# Coprocessor_Board.net
KiCad netlist of a schematic drawn in EAGLE
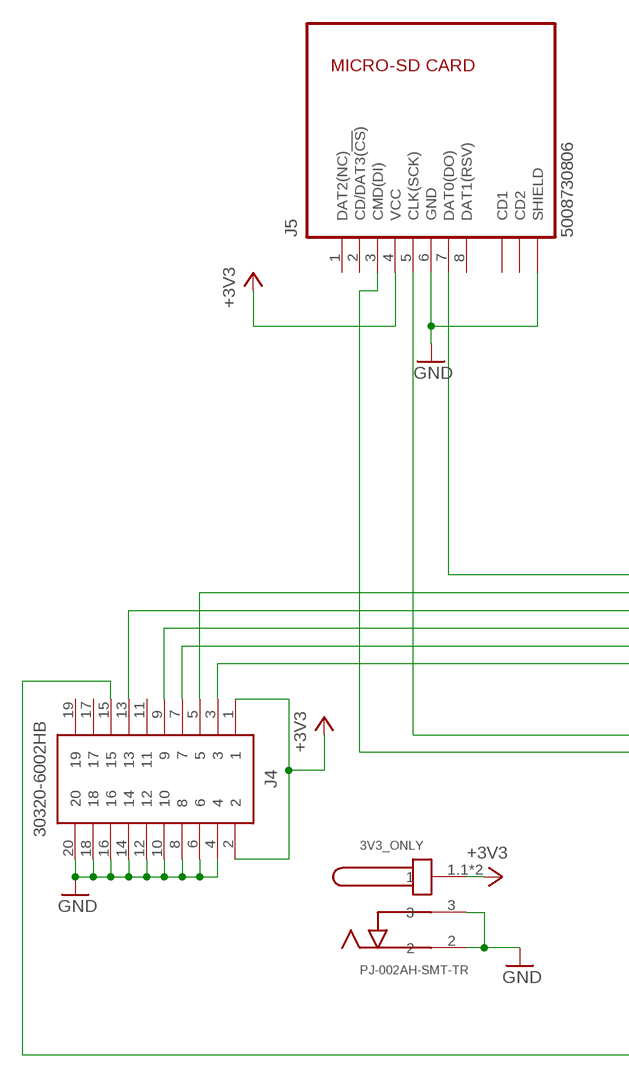
[diagram p0: schematic, sheet 1, part 1 of 2]
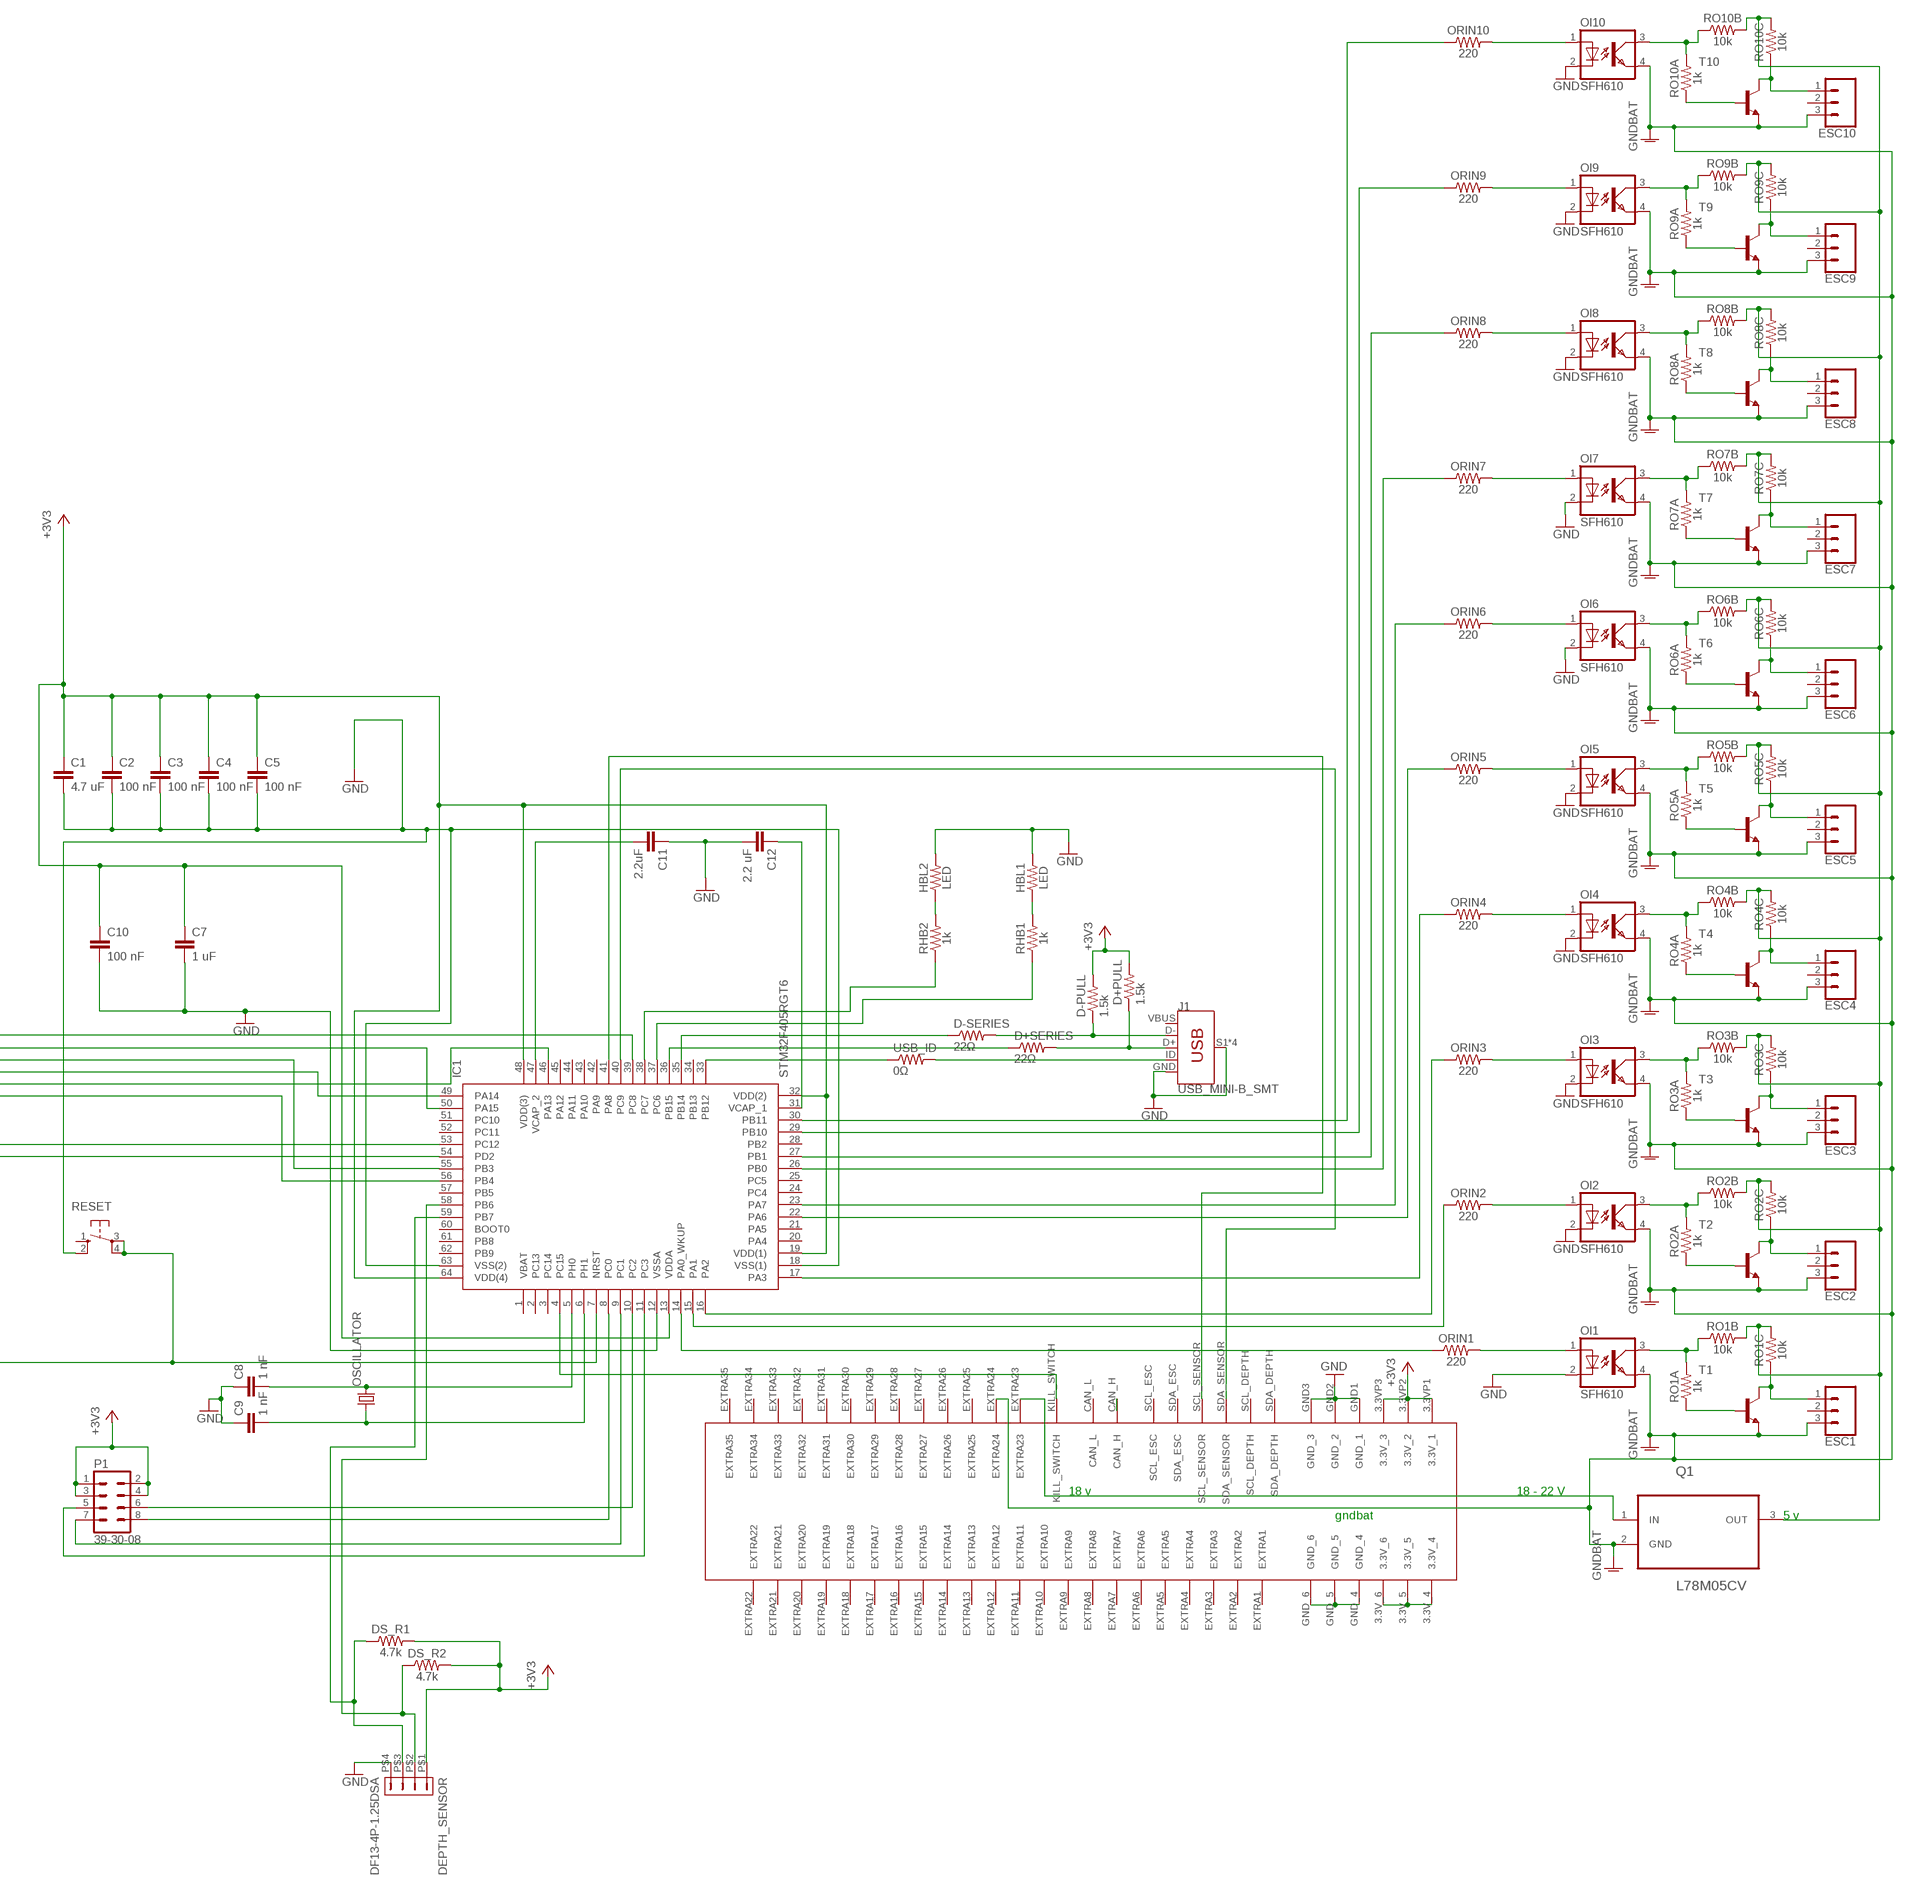
[diagram p1: schematic, sheet 1, part 2 of 2]

(export (version "E")
  (design (tool "Eeschema 10.0.6"))
  (components
    (comp (ref "3V3_ONLY")
      (value "PJ-002AH-SMT-TR")
      (footprint "eagle-import:CUI_PJ-002AH-SMT-TR")
      (fields (field (name "MF") "CUI"))
      (libsource (lib "eagle-import") (part "PJ-002AH-SMT-TR"))
    )
    (comp (ref "C1")
      (value "4.7 uF")
      (footprint "eagle-import:0603")
      (libsource (lib "eagle-import") (part "0.1UF-0603-100V-10%"))
    )
    (comp (ref "C2")
      (value "100 nF")
      (footprint "eagle-import:0603")
      (libsource (lib "eagle-import") (part "0.1UF-0603-100V-10%"))
    )
    (comp (ref "C3")
      (value "100 nF")
      (footprint "eagle-import:0603")
      (libsource (lib "eagle-import") (part "0.1UF-0603-100V-10%"))
    )
    (comp (ref "C4")
      (value "100 nF")
      (footprint "eagle-import:0603")
      (libsource (lib "eagle-import") (part "0.1UF-0603-100V-10%"))
    )
    (comp (ref "C5")
      (value "100 nF")
      (footprint "eagle-import:0603")
      (libsource (lib "eagle-import") (part "0.1UF-0603-100V-10%"))
    )
    (comp (ref "C7")
      (value "1 uF")
      (footprint "eagle-import:0603")
      (libsource (lib "eagle-import") (part "0.1UF-0603-100V-10%"))
    )
    (comp (ref "C8")
      (value "1 nF")
      (footprint "eagle-import:CAP-PTH-2.54")
      (libsource (lib "eagle-import") (part "22PF-PTH-2.54MM-200V-5%"))
    )
    (comp (ref "C9")
      (value "1 nF")
      (footprint "eagle-import:CAP-PTH-2.54")
      (libsource (lib "eagle-import") (part "22PF-PTH-2.54MM-200V-5%"))
    )
    (comp (ref "C10")
      (value "100 nF")
      (footprint "eagle-import:0603")
      (libsource (lib "eagle-import") (part "0.1UF-0603-100V-10%"))
    )
    (comp (ref "C11")
      (value "2.2uF")
      (footprint "eagle-import:0603")
      (libsource (lib "eagle-import") (part "0.1UF-0603-100V-10%"))
    )
    (comp (ref "C12")
      (value "2.2 uF")
      (footprint "eagle-import:0603")
      (libsource (lib "eagle-import") (part "0.1UF-0603-100V-10%"))
    )
    (comp (ref "D+PULL")
      (value "1.5k")
      (footprint "eagle-import:0204_7")
      (libsource (lib "eagle-import") (part "R-US_0204/7"))
    )
    (comp (ref "D+SERIES")
      (value "22Ω")
      (footprint "eagle-import:0204_7")
      (libsource (lib "eagle-import") (part "R-US_0204/7"))
    )
    (comp (ref "D-PULL")
      (value "1.5k")
      (footprint "eagle-import:0204_7")
      (libsource (lib "eagle-import") (part "R-US_0204/7"))
    )
    (comp (ref "D-SERIES")
      (value "22Ω")
      (footprint "eagle-import:0204_7")
      (libsource (lib "eagle-import") (part "R-US_0204/7"))
    )
    (comp (ref "DEPTH_SENSOR")
      (value "DF13-4P-1.25DSA")
      (footprint "eagle-import:DF13-4P-1.25DSA")
      (libsource (lib "eagle-import") (part "DF13-4P-1.25DSA"))
    )
    (comp (ref "DS_R1")
      (value "4.7k")
      (footprint "eagle-import:AXIAL-0.1")
      (libsource (lib "eagle-import") (part "1KOHM-VERT-1/4W-1%"))
    )
    (comp (ref "DS_R2")
      (value "4.7k")
      (footprint "eagle-import:AXIAL-0.1")
      (libsource (lib "eagle-import") (part "1KOHM-VERT-1/4W-1%"))
    )
    (comp (ref "ESC1")
      (value "CONN_03")
      (footprint "eagle-import:1X03")
      (libsource (lib "eagle-import") (part "CONN_03"))
    )
    (comp (ref "ESC2")
      (value "CONN_03")
      (footprint "eagle-import:1X03")
      (libsource (lib "eagle-import") (part "CONN_03"))
    )
    (comp (ref "ESC3")
      (value "CONN_03")
      (footprint "eagle-import:1X03")
      (libsource (lib "eagle-import") (part "CONN_03"))
    )
    (comp (ref "ESC4")
      (value "CONN_03")
      (footprint "eagle-import:1X03")
      (libsource (lib "eagle-import") (part "CONN_03"))
    )
    (comp (ref "ESC5")
      (value "CONN_03")
      (footprint "eagle-import:1X03")
      (libsource (lib "eagle-import") (part "CONN_03"))
    )
    (comp (ref "ESC6")
      (value "CONN_03")
      (footprint "eagle-import:1X03")
      (libsource (lib "eagle-import") (part "CONN_03"))
    )
    (comp (ref "ESC7")
      (value "CONN_03")
      (footprint "eagle-import:1X03")
      (libsource (lib "eagle-import") (part "CONN_03"))
    )
    (comp (ref "ESC8")
      (value "CONN_03")
      (footprint "eagle-import:1X03")
      (libsource (lib "eagle-import") (part "CONN_03"))
    )
    (comp (ref "ESC9")
      (value "CONN_03")
      (footprint "eagle-import:1X03")
      (libsource (lib "eagle-import") (part "CONN_03"))
    )
    (comp (ref "ESC10")
      (value "CONN_03")
      (footprint "eagle-import:1X03")
      (libsource (lib "eagle-import") (part "CONN_03"))
    )
    (comp (ref "HBL1")
      (value "LED")
      (footprint "eagle-import:AXIAL-0.1")
      (libsource (lib "eagle-import") (part "1KOHM-VERT-1/4W-1%"))
    )
    (comp (ref "HBL2")
      (value "LED")
      (footprint "eagle-import:AXIAL-0.1")
      (libsource (lib "eagle-import") (part "1KOHM-VERT-1/4W-1%"))
    )
    (comp (ref "IC1")
      (value "STM32F405RGT6")
      (footprint "eagle-import:QFP50P1200X1200X160-64N")
      (fields (field (name "RS_PART_NUMBER") "7468217"))
      (libsource (lib "eagle-import") (part "STM32F405RGT6"))
    )
    (comp (ref "J1")
      (value "USB_MINI-B_SMT")
      (footprint "eagle-import:USB-MINIB")
      (libsource (lib "eagle-import") (part "USB_MINI-B_SMT"))
    )
    (comp (ref "J4")
      (value "30320-6002HB")
      (footprint "eagle-import:SHDR20W81P254_2X10_3300X840X93")
      (fields (field (name "RS_PART_NUMBER") "8273587"))
      (libsource (lib "eagle-import") (part "30320-6002HB"))
    )
    (comp (ref "J5")
      (value "5008730806")
      (footprint "eagle-import:5008730806")
      (fields (field (name "MF") "Molex") (field (name "MP") "500873-0806"))
      (libsource (lib "eagle-import") (part "5008730806"))
    )
    (comp (ref "OI1")
      (value "SFH610")
      (footprint "eagle-import:DIL04")
      (fields (field (name "MF") "VISHAY/TELEFUNKEN") (field (name "MPN") "SFH6106-4"))
      (libsource (lib "eagle-import") (part "SFH610"))
    )
    (comp (ref "OI2")
      (value "SFH610")
      (footprint "eagle-import:DIL04")
      (fields (field (name "MF") "VISHAY/TELEFUNKEN") (field (name "MPN") "SFH6106-4"))
      (libsource (lib "eagle-import") (part "SFH610"))
    )
    (comp (ref "OI3")
      (value "SFH610")
      (footprint "eagle-import:DIL04")
      (fields (field (name "MF") "VISHAY/TELEFUNKEN") (field (name "MPN") "SFH6106-4"))
      (libsource (lib "eagle-import") (part "SFH610"))
    )
    (comp (ref "OI4")
      (value "SFH610")
      (footprint "eagle-import:DIL04")
      (fields (field (name "MF") "VISHAY/TELEFUNKEN") (field (name "MPN") "SFH6106-4"))
      (libsource (lib "eagle-import") (part "SFH610"))
    )
    (comp (ref "OI5")
      (value "SFH610")
      (footprint "eagle-import:DIL04")
      (fields (field (name "MF") "VISHAY/TELEFUNKEN") (field (name "MPN") "SFH6106-4"))
      (libsource (lib "eagle-import") (part "SFH610"))
    )
    (comp (ref "OI6")
      (value "SFH610")
      (footprint "eagle-import:DIL04")
      (fields (field (name "MF") "VISHAY/TELEFUNKEN") (field (name "MPN") "SFH6106-4"))
      (libsource (lib "eagle-import") (part "SFH610"))
    )
    (comp (ref "OI7")
      (value "SFH610")
      (footprint "eagle-import:DIL04")
      (fields (field (name "MF") "VISHAY/TELEFUNKEN") (field (name "MPN") "SFH6106-4"))
      (libsource (lib "eagle-import") (part "SFH610"))
    )
    (comp (ref "OI8")
      (value "SFH610")
      (footprint "eagle-import:DIL04")
      (fields (field (name "MF") "VISHAY/TELEFUNKEN") (field (name "MPN") "SFH6106-4"))
      (libsource (lib "eagle-import") (part "SFH610"))
    )
    (comp (ref "OI9")
      (value "SFH610")
      (footprint "eagle-import:DIL04")
      (fields (field (name "MF") "VISHAY/TELEFUNKEN") (field (name "MPN") "SFH6106-4"))
      (libsource (lib "eagle-import") (part "SFH610"))
    )
    (comp (ref "OI10")
      (value "SFH610")
      (footprint "eagle-import:DIL04")
      (fields (field (name "MF") "VISHAY/TELEFUNKEN") (field (name "MPN") "SFH6106-4"))
      (libsource (lib "eagle-import") (part "SFH610"))
    )
    (comp (ref "ORIN1")
      (value "220")
      (footprint "eagle-import:AXIAL-0.1")
      (libsource (lib "eagle-import") (part "1KOHM-VERT-1/4W-1%"))
    )
    (comp (ref "ORIN2")
      (value "220")
      (footprint "eagle-import:AXIAL-0.1")
      (libsource (lib "eagle-import") (part "1KOHM-VERT-1/4W-1%"))
    )
    (comp (ref "ORIN3")
      (value "220")
      (footprint "eagle-import:AXIAL-0.1")
      (libsource (lib "eagle-import") (part "1KOHM-VERT-1/4W-1%"))
    )
    (comp (ref "ORIN4")
      (value "220")
      (footprint "eagle-import:AXIAL-0.1")
      (libsource (lib "eagle-import") (part "1KOHM-VERT-1/4W-1%"))
    )
    (comp (ref "ORIN5")
      (value "220")
      (footprint "eagle-import:AXIAL-0.1")
      (libsource (lib "eagle-import") (part "1KOHM-VERT-1/4W-1%"))
    )
    (comp (ref "ORIN6")
      (value "220")
      (footprint "eagle-import:AXIAL-0.1")
      (libsource (lib "eagle-import") (part "1KOHM-VERT-1/4W-1%"))
    )
    (comp (ref "ORIN7")
      (value "220")
      (footprint "eagle-import:AXIAL-0.1")
      (libsource (lib "eagle-import") (part "1KOHM-VERT-1/4W-1%"))
    )
    (comp (ref "ORIN8")
      (value "220")
      (footprint "eagle-import:AXIAL-0.1")
      (libsource (lib "eagle-import") (part "1KOHM-VERT-1/4W-1%"))
    )
    (comp (ref "ORIN9")
      (value "220")
      (footprint "eagle-import:AXIAL-0.1")
      (libsource (lib "eagle-import") (part "1KOHM-VERT-1/4W-1%"))
    )
    (comp (ref "ORIN10")
      (value "220")
      (footprint "eagle-import:AXIAL-0.1")
      (libsource (lib "eagle-import") (part "1KOHM-VERT-1/4W-1%"))
    )
    (comp (ref "OSCILLATOR")
      (value "CRYSTALHC49S")
      (footprint "eagle-import:HC49_S")
      (libsource (lib "eagle-import") (part "CRYSTALHC49S"))
    )
    (comp (ref "P1")
      (value "39-30-08")
      (footprint "eagle-import:39-30-_08_")
      (libsource (lib "eagle-import") (part "39-30-?08?"))
    )
    (comp (ref "Q1")
      (value "L78M05CV")
      (footprint "eagle-import:TO254P450X1020X1935-3P")
      (fields (field (name "MF") "STMicroelectronics"))
      (libsource (lib "eagle-import") (part "L78M05CV"))
    )
    (comp (ref "RESET")
      (value "10-XX")
      (footprint "eagle-import:B3F-10XX")
      (fields (field (name "MPN") "B3F-1000"))
      (libsource (lib "eagle-import") (part "10-XX"))
    )
    (comp (ref "RHB1")
      (value "1k")
      (footprint "eagle-import:AXIAL-0.3")
      (libsource (lib "eagle-import") (part "1KOHM-HORIZ-1/4W-1%"))
    )
    (comp (ref "RHB2")
      (value "1k")
      (footprint "eagle-import:AXIAL-0.3")
      (libsource (lib "eagle-import") (part "1KOHM-HORIZ-1/4W-5%"))
    )
    (comp (ref "RO1A")
      (value "1k")
      (footprint "eagle-import:0603")
      (libsource (lib "eagle-import") (part "1KOHM-0603-1/10W-1%"))
    )
    (comp (ref "RO1B")
      (value "10k")
      (footprint "eagle-import:0603")
      (libsource (lib "eagle-import") (part "1KOHM-0603-1/10W-1%"))
    )
    (comp (ref "RO1C")
      (value "10k")
      (footprint "eagle-import:0603")
      (libsource (lib "eagle-import") (part "1KOHM-0603-1/10W-1%"))
    )
    (comp (ref "RO2A")
      (value "1k")
      (footprint "eagle-import:0603")
      (libsource (lib "eagle-import") (part "1KOHM-0603-1/10W-1%"))
    )
    (comp (ref "RO2B")
      (value "10k")
      (footprint "eagle-import:0603")
      (libsource (lib "eagle-import") (part "1KOHM-0603-1/10W-1%"))
    )
    (comp (ref "RO2C")
      (value "10k")
      (footprint "eagle-import:0603")
      (libsource (lib "eagle-import") (part "1KOHM-0603-1/10W-1%"))
    )
    (comp (ref "RO3A")
      (value "1k")
      (footprint "eagle-import:0603")
      (libsource (lib "eagle-import") (part "1KOHM-0603-1/10W-1%"))
    )
    (comp (ref "RO3B")
      (value "10k")
      (footprint "eagle-import:0603")
      (libsource (lib "eagle-import") (part "1KOHM-0603-1/10W-1%"))
    )
    (comp (ref "RO3C")
      (value "10k")
      (footprint "eagle-import:0603")
      (libsource (lib "eagle-import") (part "1KOHM-0603-1/10W-1%"))
    )
    (comp (ref "RO4A")
      (value "1k")
      (footprint "eagle-import:0603")
      (libsource (lib "eagle-import") (part "1KOHM-0603-1/10W-1%"))
    )
    (comp (ref "RO4B")
      (value "10k")
      (footprint "eagle-import:0603")
      (libsource (lib "eagle-import") (part "1KOHM-0603-1/10W-1%"))
    )
    (comp (ref "RO4C")
      (value "10k")
      (footprint "eagle-import:0603")
      (libsource (lib "eagle-import") (part "1KOHM-0603-1/10W-1%"))
    )
    (comp (ref "RO5A")
      (value "1k")
      (footprint "eagle-import:0603")
      (libsource (lib "eagle-import") (part "1KOHM-0603-1/10W-1%"))
    )
    (comp (ref "RO5B")
      (value "10k")
      (footprint "eagle-import:0603")
      (libsource (lib "eagle-import") (part "1KOHM-0603-1/10W-1%"))
    )
    (comp (ref "RO5C")
      (value "10k")
      (footprint "eagle-import:0603")
      (libsource (lib "eagle-import") (part "1KOHM-0603-1/10W-1%"))
    )
    (comp (ref "RO6A")
      (value "1k")
      (footprint "eagle-import:0603")
      (libsource (lib "eagle-import") (part "1KOHM-0603-1/10W-1%"))
    )
    (comp (ref "RO6B")
      (value "10k")
      (footprint "eagle-import:0603")
      (libsource (lib "eagle-import") (part "1KOHM-0603-1/10W-1%"))
    )
    (comp (ref "RO6C")
      (value "10k")
      (footprint "eagle-import:0603")
      (libsource (lib "eagle-import") (part "1KOHM-0603-1/10W-1%"))
    )
    (comp (ref "RO7A")
      (value "1k")
      (footprint "eagle-import:0603")
      (libsource (lib "eagle-import") (part "1KOHM-0603-1/10W-1%"))
    )
    (comp (ref "RO7B")
      (value "10k")
      (footprint "eagle-import:0603")
      (libsource (lib "eagle-import") (part "1KOHM-0603-1/10W-1%"))
    )
    (comp (ref "RO7C")
      (value "10k")
      (footprint "eagle-import:0603")
      (libsource (lib "eagle-import") (part "1KOHM-0603-1/10W-1%"))
    )
    (comp (ref "RO8A")
      (value "1k")
      (footprint "eagle-import:0603")
      (libsource (lib "eagle-import") (part "1KOHM-0603-1/10W-1%"))
    )
    (comp (ref "RO8B")
      (value "10k")
      (footprint "eagle-import:0603")
      (libsource (lib "eagle-import") (part "1KOHM-0603-1/10W-1%"))
    )
    (comp (ref "RO8C")
      (value "10k")
      (footprint "eagle-import:0603")
      (libsource (lib "eagle-import") (part "1KOHM-0603-1/10W-1%"))
    )
    (comp (ref "RO9A")
      (value "1k")
      (footprint "eagle-import:0603")
      (libsource (lib "eagle-import") (part "1KOHM-0603-1/10W-1%"))
    )
    (comp (ref "RO9B")
      (value "10k")
      (footprint "eagle-import:0603")
      (libsource (lib "eagle-import") (part "1KOHM-0603-1/10W-1%"))
    )
    (comp (ref "RO9C")
      (value "10k")
      (footprint "eagle-import:0603")
      (libsource (lib "eagle-import") (part "1KOHM-0603-1/10W-1%"))
    )
    (comp (ref "RO10A")
      (value "1k")
      (footprint "eagle-import:0603")
      (libsource (lib "eagle-import") (part "1KOHM-0603-1/10W-1%"))
    )
    (comp (ref "RO10B")
      (value "10k")
      (footprint "eagle-import:0603")
      (libsource (lib "eagle-import") (part "1KOHM-0603-1/10W-1%"))
    )
    (comp (ref "RO10C")
      (value "10k")
      (footprint "eagle-import:0603")
      (libsource (lib "eagle-import") (part "1KOHM-0603-1/10W-1%"))
    )
    (comp (ref "T1")
      (value "-NPN-TO126V")
      (footprint "eagle-import:TO126V")
      (libsource (lib "eagle-import") (part "-NPN-TO126V"))
    )
    (comp (ref "T2")
      (value "-NPN-TO126V")
      (footprint "eagle-import:TO126V")
      (libsource (lib "eagle-import") (part "-NPN-TO126V"))
    )
    (comp (ref "T3")
      (value "-NPN-TO126V")
      (footprint "eagle-import:TO126V")
      (libsource (lib "eagle-import") (part "-NPN-TO126V"))
    )
    (comp (ref "T4")
      (value "-NPN-TO126V")
      (footprint "eagle-import:TO126V")
      (libsource (lib "eagle-import") (part "-NPN-TO126V"))
    )
    (comp (ref "T5")
      (value "-NPN-TO126V")
      (footprint "eagle-import:TO126V")
      (libsource (lib "eagle-import") (part "-NPN-TO126V"))
    )
    (comp (ref "T6")
      (value "-NPN-TO126V")
      (footprint "eagle-import:TO126V")
      (libsource (lib "eagle-import") (part "-NPN-TO126V"))
    )
    (comp (ref "T7")
      (value "-NPN-TO126V")
      (footprint "eagle-import:TO126V")
      (libsource (lib "eagle-import") (part "-NPN-TO126V"))
    )
    (comp (ref "T8")
      (value "-NPN-TO126V")
      (footprint "eagle-import:TO126V")
      (libsource (lib "eagle-import") (part "-NPN-TO126V"))
    )
    (comp (ref "T9")
      (value "-NPN-TO126V")
      (footprint "eagle-import:TO126V")
      (libsource (lib "eagle-import") (part "-NPN-TO126V"))
    )
    (comp (ref "T10")
      (value "-NPN-TO126V")
      (footprint "eagle-import:TO126V")
      (libsource (lib "eagle-import") (part "-NPN-TO126V"))
    )
    (comp (ref "U$1")
      (value "5530843")
      (footprint "eagle-import:5530843-6-BOARDFINGERS")
      (libsource (lib "eagle-import") (part "5530843"))
    )
    (comp (ref "USB_ID")
      (value "0Ω")
      (footprint "eagle-import:0204_7")
      (libsource (lib "eagle-import") (part "R-US_0204/7"))
    )
  )
  (nets
    (net (code "1") (name "+3V3") (class "Default")
      (node (ref "3V3_ONLY") (pin "1.1") (pinfunction "1_1.1") (pintype "passive"))
      (node (ref "3V3_ONLY") (pin "1.2") (pinfunction "1_1.2") (pintype "passive"))
      (node (ref "C1") (pin "1") (pinfunction "1_1") (pintype "passive"))
      (node (ref "C10") (pin "1") (pinfunction "1_1") (pintype "passive"))
      (node (ref "C2") (pin "1") (pinfunction "1_1") (pintype "passive"))
      (node (ref "C3") (pin "1") (pinfunction "1_1") (pintype "passive"))
      (node (ref "C4") (pin "1") (pinfunction "1_1") (pintype "passive"))
      (node (ref "C5") (pin "1") (pinfunction "1_1") (pintype "passive"))
      (node (ref "C7") (pin "1") (pinfunction "1_1") (pintype "passive"))
      (node (ref "D+PULL") (pin "2") (pinfunction "2_2") (pintype "passive"))
      (node (ref "D-PULL") (pin "2") (pinfunction "2_2") (pintype "passive"))
      (node (ref "DEPTH_SENSOR") (pin "P$1") (pinfunction "1_P$1") (pintype "passive"))
      (node (ref "DS_R1") (pin "P$2") (pinfunction "2_P$2") (pintype "passive"))
      (node (ref "DS_R2") (pin "P$2") (pinfunction "2_P$2") (pintype "passive"))
      (node (ref "IC1") (pin "13") (pinfunction "VDDA_13") (pintype "power_in"))
      (node (ref "IC1") (pin "19") (pinfunction "VDD(1)_19") (pintype "power_in"))
      (node (ref "IC1") (pin "32") (pinfunction "VDD(2)_32") (pintype "power_in"))
      (node (ref "IC1") (pin "48") (pinfunction "VDD(3)_48") (pintype "power_in"))
      (node (ref "IC1") (pin "64") (pinfunction "VDD(4)_64") (pintype "power_in"))
      (node (ref "J4") (pin "1") (pinfunction "1_1") (pintype "passive"))
      (node (ref "J4") (pin "2") (pinfunction "2_2") (pintype "passive"))
      (node (ref "J5") (pin "4") (pinfunction "VCC_4") (pintype "bidirectional"))
      (node (ref "P1") (pin "1") (pinfunction "1_1") (pintype "passive"))
      (node (ref "P1") (pin "2") (pinfunction "2_2") (pintype "passive"))
      (node (ref "P1") (pin "3") (pinfunction "3_3") (pintype "passive"))
      (node (ref "P1") (pin "4") (pinfunction "4_4") (pintype "passive"))
      (node (ref "U$1") (pin "3.3VP1") (pinfunction "3.3V_1_3.3VP1") (pintype "bidirectional"))
      (node (ref "U$1") (pin "3.3VP2") (pinfunction "3.3V_2_3.3VP2") (pintype "bidirectional"))
      (node (ref "U$1") (pin "3.3VP3") (pinfunction "3.3V_3_3.3VP3") (pintype "bidirectional"))
      (node (ref "U$1") (pin "3.3V_4") (pinfunction "3.3V_4_3.3V_4") (pintype "bidirectional"))
      (node (ref "U$1") (pin "3.3V_5") (pinfunction "3.3V_5_3.3V_5") (pintype "bidirectional"))
      (node (ref "U$1") (pin "3.3V_6") (pinfunction "3.3V_6_3.3V_6") (pintype "bidirectional"))
    )
    (net (code "2") (name "/VBUS") (class "Default")
      (node (ref "J1") (pin "VBUS") (pinfunction "VBUS_VBUS") (pintype "power_in"))
    )
    (net (code "3") (name "GND") (class "Default")
      (node (ref "3V3_ONLY") (pin "2") (pinfunction "2_2") (pintype "passive"))
      (node (ref "3V3_ONLY") (pin "3") (pinfunction "3_3") (pintype "passive"))
      (node (ref "C1") (pin "2") (pinfunction "2_2") (pintype "passive"))
      (node (ref "C10") (pin "2") (pinfunction "2_2") (pintype "passive"))
      (node (ref "C11") (pin "1") (pinfunction "1_1") (pintype "passive"))
      (node (ref "C12") (pin "2") (pinfunction "2_2") (pintype "passive"))
      (node (ref "C2") (pin "2") (pinfunction "2_2") (pintype "passive"))
      (node (ref "C3") (pin "2") (pinfunction "2_2") (pintype "passive"))
      (node (ref "C4") (pin "2") (pinfunction "2_2") (pintype "passive"))
      (node (ref "C5") (pin "2") (pinfunction "2_2") (pintype "passive"))
      (node (ref "C7") (pin "2") (pinfunction "2_2") (pintype "passive"))
      (node (ref "C8") (pin "1") (pinfunction "1_1") (pintype "passive"))
      (node (ref "C9") (pin "1") (pinfunction "1_1") (pintype "passive"))
      (node (ref "DEPTH_SENSOR") (pin "P$4") (pinfunction "4_P$4") (pintype "passive"))
      (node (ref "HBL1") (pin "P$2") (pinfunction "2_P$2") (pintype "passive"))
      (node (ref "HBL2") (pin "P$2") (pinfunction "2_P$2") (pintype "passive"))
      (node (ref "IC1") (pin "12") (pinfunction "VSSA_12") (pintype "power_in"))
      (node (ref "IC1") (pin "18") (pinfunction "VSS(1)_18") (pintype "power_in"))
      (node (ref "IC1") (pin "63") (pinfunction "VSS(2)_63") (pintype "power_in"))
      (node (ref "J1") (pin "GND") (pinfunction "GND_GND") (pintype "power_in"))
      (node (ref "J1") (pin "S1") (pinfunction "SHIELD_S1") (pintype "bidirectional"))
      (node (ref "J1") (pin "S2") (pinfunction "SHIELD_S2") (pintype "bidirectional"))
      (node (ref "J1") (pin "S3") (pinfunction "SHIELD_S3") (pintype "bidirectional"))
      (node (ref "J1") (pin "S4") (pinfunction "SHIELD_S4") (pintype "bidirectional"))
      (node (ref "J4") (pin "10") (pinfunction "10_10") (pintype "passive"))
      (node (ref "J4") (pin "12") (pinfunction "12_12") (pintype "passive"))
      (node (ref "J4") (pin "14") (pinfunction "14_14") (pintype "passive"))
      (node (ref "J4") (pin "16") (pinfunction "16_16") (pintype "passive"))
      (node (ref "J4") (pin "18") (pinfunction "18_18") (pintype "passive"))
      (node (ref "J4") (pin "20") (pinfunction "20_20") (pintype "passive"))
      (node (ref "J4") (pin "4") (pinfunction "4_4") (pintype "passive"))
      (node (ref "J4") (pin "6") (pinfunction "6_6") (pintype "passive"))
      (node (ref "J4") (pin "8") (pinfunction "8_8") (pintype "passive"))
      (node (ref "J5") (pin "6") (pinfunction "GND_6") (pintype "bidirectional"))
      (node (ref "J5") (pin "S3") (pinfunction "SHIELD_S3") (pintype "bidirectional"))
      (node (ref "J5") (pin "S4") (pinfunction "SHIELD_S4") (pintype "bidirectional"))
      (node (ref "OI1") (pin "2") (pinfunction "C_2") (pintype "passive"))
      (node (ref "OI10") (pin "2") (pinfunction "C_2") (pintype "passive"))
      (node (ref "OI2") (pin "2") (pinfunction "C_2") (pintype "passive"))
      (node (ref "OI3") (pin "2") (pinfunction "C_2") (pintype "passive"))
      (node (ref "OI4") (pin "2") (pinfunction "C_2") (pintype "passive"))
      (node (ref "OI5") (pin "2") (pinfunction "C_2") (pintype "passive"))
      (node (ref "OI6") (pin "2") (pinfunction "C_2") (pintype "passive"))
      (node (ref "OI7") (pin "2") (pinfunction "C_2") (pintype "passive"))
      (node (ref "OI8") (pin "2") (pinfunction "C_2") (pintype "passive"))
      (node (ref "OI9") (pin "2") (pinfunction "C_2") (pintype "passive"))
      (node (ref "RESET") (pin "2") (pinfunction "S1_2") (pintype "passive"))
      (node (ref "U$1") (pin "GND1") (pinfunction "GND_1_GND1") (pintype "bidirectional"))
      (node (ref "U$1") (pin "GND2") (pinfunction "GND_2_GND2") (pintype "bidirectional"))
      (node (ref "U$1") (pin "GND3") (pinfunction "GND_3_GND3") (pintype "bidirectional"))
      (node (ref "U$1") (pin "GND_4") (pinfunction "GND_4_GND_4") (pintype "bidirectional"))
      (node (ref "U$1") (pin "GND_5") (pinfunction "GND_5_GND_5") (pintype "bidirectional"))
      (node (ref "U$1") (pin "GND_6") (pinfunction "GND_6_GND_6") (pintype "bidirectional"))
    )
    (net (code "4") (name "GNDBAT") (class "Default")
      (node (ref "ESC1") (pin "3") (pinfunction "3_3") (pintype "passive"))
      (node (ref "ESC10") (pin "3") (pinfunction "3_3") (pintype "passive"))
      (node (ref "ESC2") (pin "3") (pinfunction "3_3") (pintype "passive"))
      (node (ref "ESC3") (pin "3") (pinfunction "3_3") (pintype "passive"))
      (node (ref "ESC4") (pin "3") (pinfunction "3_3") (pintype "passive"))
      (node (ref "ESC5") (pin "3") (pinfunction "3_3") (pintype "passive"))
      (node (ref "ESC6") (pin "3") (pinfunction "3_3") (pintype "passive"))
      (node (ref "ESC7") (pin "3") (pinfunction "3_3") (pintype "passive"))
      (node (ref "ESC8") (pin "3") (pinfunction "3_3") (pintype "passive"))
      (node (ref "ESC9") (pin "3") (pinfunction "3_3") (pintype "passive"))
      (node (ref "OI1") (pin "4") (pinfunction "EMIT_4") (pintype "passive"))
      (node (ref "OI10") (pin "4") (pinfunction "EMIT_4") (pintype "passive"))
      (node (ref "OI2") (pin "4") (pinfunction "EMIT_4") (pintype "passive"))
      (node (ref "OI3") (pin "4") (pinfunction "EMIT_4") (pintype "passive"))
      (node (ref "OI4") (pin "4") (pinfunction "EMIT_4") (pintype "passive"))
      (node (ref "OI5") (pin "4") (pinfunction "EMIT_4") (pintype "passive"))
      (node (ref "OI6") (pin "4") (pinfunction "EMIT_4") (pintype "passive"))
      (node (ref "OI7") (pin "4") (pinfunction "EMIT_4") (pintype "passive"))
      (node (ref "OI8") (pin "4") (pinfunction "EMIT_4") (pintype "passive"))
      (node (ref "OI9") (pin "4") (pinfunction "EMIT_4") (pintype "passive"))
      (node (ref "Q1") (pin "2") (pinfunction "GND_2") (pintype "passive"))
      (node (ref "T1") (pin "1") (pinfunction "E_1") (pintype "passive"))
      (node (ref "T10") (pin "1") (pinfunction "E_1") (pintype "passive"))
      (node (ref "T2") (pin "1") (pinfunction "E_1") (pintype "passive"))
      (node (ref "T3") (pin "1") (pinfunction "E_1") (pintype "passive"))
      (node (ref "T4") (pin "1") (pinfunction "E_1") (pintype "passive"))
      (node (ref "T5") (pin "1") (pinfunction "E_1") (pintype "passive"))
      (node (ref "T6") (pin "1") (pinfunction "E_1") (pintype "passive"))
      (node (ref "T7") (pin "1") (pinfunction "E_1") (pintype "passive"))
      (node (ref "T8") (pin "1") (pinfunction "E_1") (pintype "passive"))
      (node (ref "T9") (pin "1") (pinfunction "E_1") (pintype "passive"))
      (node (ref "U$1") (pin "EXTRA24") (pinfunction "EXTRA24_EXTRA24") (pintype "bidirectional"))
    )
    (net (code "5") (name "Net-(D+PULL-Pad1)") (class "Default")
      (node (ref "D+PULL") (pin "1") (pinfunction "1_1") (pintype "passive"))
      (node (ref "D+SERIES") (pin "2") (pinfunction "2_2") (pintype "passive"))
      (node (ref "J1") (pin "D+") (pinfunction "D+_D+") (pintype "bidirectional"))
    )
    (net (code "6") (name "Net-(D-PULL-Pad1)") (class "Default")
      (node (ref "D-PULL") (pin "1") (pinfunction "1_1") (pintype "passive"))
      (node (ref "D-SERIES") (pin "2") (pinfunction "2_2") (pintype "passive"))
      (node (ref "J1") (pin "D-") (pinfunction "D-_D-") (pintype "bidirectional"))
    )
    (net (code "7") (name "Net-(DEPTH_SENSOR-2)") (class "Default")
      (node (ref "DEPTH_SENSOR") (pin "P$2") (pinfunction "2_P$2") (pintype "passive"))
      (node (ref "DS_R2") (pin "P$1") (pinfunction "1_P$1") (pintype "passive"))
      (node (ref "IC1") (pin "58") (pinfunction "PB6_58") (pintype "passive"))
    )
    (net (code "8") (name "Net-(DEPTH_SENSOR-3)") (class "Default")
      (node (ref "DEPTH_SENSOR") (pin "P$3") (pinfunction "3_P$3") (pintype "passive"))
      (node (ref "DS_R1") (pin "P$1") (pinfunction "1_P$1") (pintype "passive"))
      (node (ref "IC1") (pin "59") (pinfunction "PB7_59") (pintype "passive"))
    )
    (net (code "9") (name "Net-(HBL1-1)") (class "Default")
      (node (ref "HBL1") (pin "P$1") (pinfunction "1_P$1") (pintype "passive"))
      (node (ref "RHB1") (pin "P$2") (pinfunction "2_P$2") (pintype "passive"))
    )
    (net (code "10") (name "Net-(HBL2-1)") (class "Default")
      (node (ref "HBL2") (pin "P$1") (pinfunction "1_P$1") (pintype "passive"))
      (node (ref "RHB2") (pin "P$2") (pinfunction "2_P$2") (pintype "passive"))
    )
    (net (code "11") (name "Net-(IC1-NRST)") (class "Default")
      (node (ref "IC1") (pin "7") (pinfunction "NRST_7") (pintype "input"))
      (node (ref "J4") (pin "15") (pinfunction "15_15") (pintype "passive"))
      (node (ref "RESET") (pin "3") (pinfunction "P_3") (pintype "passive"))
      (node (ref "RESET") (pin "4") (pinfunction "P1_4") (pintype "passive"))
    )
    (net (code "12") (name "Net-(IC1-PA0_WKUP)") (class "Default")
      (node (ref "IC1") (pin "14") (pinfunction "PA0_WKUP_14") (pintype "passive"))
      (node (ref "ORIN1") (pin "P$1") (pinfunction "1_P$1") (pintype "passive"))
    )
    (net (code "13") (name "Net-(IC1-PA1)") (class "Default")
      (node (ref "IC1") (pin "15") (pinfunction "PA1_15") (pintype "passive"))
      (node (ref "ORIN2") (pin "P$1") (pinfunction "1_P$1") (pintype "passive"))
    )
    (net (code "14") (name "Net-(IC1-PA2)") (class "Default")
      (node (ref "IC1") (pin "16") (pinfunction "PA2_16") (pintype "passive"))
      (node (ref "ORIN3") (pin "P$1") (pinfunction "1_P$1") (pintype "passive"))
    )
    (net (code "15") (name "Net-(IC1-PA3)") (class "Default")
      (node (ref "IC1") (pin "17") (pinfunction "PA3_17") (pintype "passive"))
      (node (ref "ORIN4") (pin "P$1") (pinfunction "1_P$1") (pintype "passive"))
    )
    (net (code "16") (name "Net-(IC1-PA6)") (class "Default")
      (node (ref "IC1") (pin "22") (pinfunction "PA6_22") (pintype "passive"))
      (node (ref "ORIN5") (pin "P$1") (pinfunction "1_P$1") (pintype "passive"))
    )
    (net (code "17") (name "Net-(IC1-PA7)") (class "Default")
      (node (ref "IC1") (pin "23") (pinfunction "PA7_23") (pintype "passive"))
      (node (ref "ORIN6") (pin "P$1") (pinfunction "1_P$1") (pintype "passive"))
    )
    (net (code "18") (name "Net-(IC1-PA8)") (class "Default")
      (node (ref "IC1") (pin "41") (pinfunction "PA8_41") (pintype "passive"))
      (node (ref "U$1") (pin "SCL_SENSOR") (pinfunction "SCL_SENSOR_SCL_SENSOR") (pintype "bidirectional"))
    )
    (net (code "19") (name "Net-(IC1-PA13)") (class "Default")
      (node (ref "IC1") (pin "46") (pinfunction "PA13_46") (pintype "passive"))
      (node (ref "J4") (pin "7") (pinfunction "7_7") (pintype "passive"))
    )
    (net (code "20") (name "Net-(IC1-PA14)") (class "Default")
      (node (ref "IC1") (pin "49") (pinfunction "PA14_49") (pintype "passive"))
      (node (ref "J4") (pin "9") (pinfunction "9_9") (pintype "passive"))
    )
    (net (code "21") (name "Net-(IC1-PA15)") (class "Default")
      (node (ref "IC1") (pin "50") (pinfunction "PA15_50") (pintype "passive"))
      (node (ref "J4") (pin "5") (pinfunction "5_5") (pintype "passive"))
    )
    (net (code "22") (name "Net-(IC1-PB0)") (class "Default")
      (node (ref "IC1") (pin "26") (pinfunction "PB0_26") (pintype "passive"))
      (node (ref "ORIN7") (pin "P$1") (pinfunction "1_P$1") (pintype "passive"))
    )
    (net (code "23") (name "Net-(IC1-PB1)") (class "Default")
      (node (ref "IC1") (pin "27") (pinfunction "PB1_27") (pintype "passive"))
      (node (ref "ORIN8") (pin "P$1") (pinfunction "1_P$1") (pintype "passive"))
    )
    (net (code "24") (name "Net-(IC1-PB3)") (class "Default")
      (node (ref "IC1") (pin "55") (pinfunction "PB3_55") (pintype "passive"))
      (node (ref "J4") (pin "13") (pinfunction "13_13") (pintype "passive"))
    )
    (net (code "25") (name "Net-(IC1-PB4)") (class "Default")
      (node (ref "IC1") (pin "56") (pinfunction "PB4_56") (pintype "passive"))
      (node (ref "J4") (pin "3") (pinfunction "3_3") (pintype "passive"))
    )
    (net (code "26") (name "Net-(IC1-PB10)") (class "Default")
      (node (ref "IC1") (pin "29") (pinfunction "PB10_29") (pintype "passive"))
      (node (ref "ORIN9") (pin "P$1") (pinfunction "1_P$1") (pintype "passive"))
    )
    (net (code "27") (name "Net-(IC1-PB11)") (class "Default")
      (node (ref "IC1") (pin "30") (pinfunction "PB11_30") (pintype "passive"))
      (node (ref "ORIN10") (pin "P$1") (pinfunction "1_P$1") (pintype "passive"))
    )
    (net (code "28") (name "Net-(IC1-PB12)") (class "Default")
      (node (ref "IC1") (pin "33") (pinfunction "PB12_33") (pintype "passive"))
      (node (ref "USB_ID") (pin "1") (pinfunction "1_1") (pintype "passive"))
    )
    (net (code "29") (name "Net-(IC1-PB14)") (class "Default")
      (node (ref "D-SERIES") (pin "1") (pinfunction "1_1") (pintype "passive"))
      (node (ref "IC1") (pin "35") (pinfunction "PB14_35") (pintype "passive"))
    )
    (net (code "30") (name "Net-(IC1-PB15)") (class "Default")
      (node (ref "D+SERIES") (pin "1") (pinfunction "1_1") (pintype "passive"))
      (node (ref "IC1") (pin "36") (pinfunction "PB15_36") (pintype "passive"))
    )
    (net (code "31") (name "Net-(IC1-PC0)") (class "Default")
      (node (ref "IC1") (pin "8") (pinfunction "PC0_8") (pintype "passive"))
      (node (ref "P1") (pin "8") (pinfunction "8_8") (pintype "passive"))
    )
    (net (code "32") (name "Net-(IC1-PC1)") (class "Default")
      (node (ref "IC1") (pin "9") (pinfunction "PC1_9") (pintype "passive"))
      (node (ref "P1") (pin "7") (pinfunction "7_7") (pintype "passive"))
    )
    (net (code "33") (name "Net-(IC1-PC2)") (class "Default")
      (node (ref "IC1") (pin "10") (pinfunction "PC2_10") (pintype "passive"))
      (node (ref "P1") (pin "6") (pinfunction "6_6") (pintype "passive"))
    )
    (net (code "34") (name "Net-(IC1-PC3)") (class "Default")
      (node (ref "IC1") (pin "11") (pinfunction "PC3_11") (pintype "passive"))
      (node (ref "P1") (pin "5") (pinfunction "5_5") (pintype "passive"))
    )
    (net (code "35") (name "Net-(IC1-PC6)") (class "Default")
      (node (ref "IC1") (pin "37") (pinfunction "PC6_37") (pintype "passive"))
      (node (ref "RHB1") (pin "P$1") (pinfunction "1_P$1") (pintype "passive"))
    )
    (net (code "36") (name "Net-(IC1-PC7)") (class "Default")
      (node (ref "IC1") (pin "38") (pinfunction "PC7_38") (pintype "passive"))
      (node (ref "RHB2") (pin "P$1") (pinfunction "1_P$1") (pintype "passive"))
    )
    (net (code "37") (name "Net-(IC1-PC8)") (class "Default")
      (node (ref "IC1") (pin "39") (pinfunction "PC8_39") (pintype "passive"))
      (node (ref "J5") (pin "7") (pinfunction "DAT0(DO)_7") (pintype "bidirectional"))
    )
    (net (code "38") (name "Net-(IC1-PC9)") (class "Default")
      (node (ref "IC1") (pin "40") (pinfunction "PC9_40") (pintype "passive"))
      (node (ref "U$1") (pin "SDA_SENSOR") (pinfunction "SDA_SENSOR_SDA_SENSOR") (pintype "bidirectional"))
    )
    (net (code "39") (name "Net-(IC1-PC12)") (class "Default")
      (node (ref "IC1") (pin "53") (pinfunction "PC12_53") (pintype "passive"))
      (node (ref "J5") (pin "5") (pinfunction "CLK(SCK)_5") (pintype "bidirectional"))
    )
    (net (code "40") (name "Net-(IC1-PC15)") (class "Default")
      (node (ref "IC1") (pin "4") (pinfunction "PC15_4") (pintype "passive"))
      (node (ref "U$1") (pin "KILL_SWITCH") (pinfunction "KILL_SWITCH_KILL_SWITCH") (pintype "bidirectional"))
    )
    (net (code "41") (name "Net-(IC1-PD2)") (class "Default")
      (node (ref "IC1") (pin "54") (pinfunction "PD2_54") (pintype "passive"))
      (node (ref "J5") (pin "3") (pinfunction "CMD(DI)_3") (pintype "bidirectional"))
    )
    (net (code "42") (name "Net-(IC1-PH0)") (class "Default")
      (node (ref "C8") (pin "2") (pinfunction "2_2") (pintype "passive"))
      (node (ref "IC1") (pin "5") (pinfunction "PH0_5") (pintype "passive"))
      (node (ref "OSCILLATOR") (pin "2") (pinfunction "2_2") (pintype "passive"))
    )
    (net (code "43") (name "Net-(IC1-PH1)") (class "Default")
      (node (ref "C9") (pin "2") (pinfunction "2_2") (pintype "passive"))
      (node (ref "IC1") (pin "6") (pinfunction "PH1_6") (pintype "passive"))
      (node (ref "OSCILLATOR") (pin "1") (pinfunction "1_1") (pintype "passive"))
    )
    (net (code "44") (name "Net-(IC1-VCAP_1)") (class "Default")
      (node (ref "C12") (pin "1") (pinfunction "1_1") (pintype "passive"))
      (node (ref "IC1") (pin "31") (pinfunction "VCAP_1_31") (pintype "passive"))
    )
    (net (code "45") (name "Net-(IC1-VCAP_2)") (class "Default")
      (node (ref "C11") (pin "2") (pinfunction "2_2") (pintype "passive"))
      (node (ref "IC1") (pin "47") (pinfunction "VCAP_2_47") (pintype "passive"))
    )
    (net (code "46") (name "Net-(J1-PadID)") (class "Default")
      (node (ref "J1") (pin "ID") (pinfunction "ID_ID") (pintype "bidirectional"))
      (node (ref "USB_ID") (pin "2") (pinfunction "2_2") (pintype "passive"))
    )
    (net (code "47") (name "Net-(OI1-A)") (class "Default")
      (node (ref "OI1") (pin "1") (pinfunction "A_1") (pintype "passive"))
      (node (ref "ORIN1") (pin "P$2") (pinfunction "2_P$2") (pintype "passive"))
    )
    (net (code "48") (name "Net-(OI1-COL)") (class "Default")
      (node (ref "OI1") (pin "3") (pinfunction "COL_3") (pintype "passive"))
      (node (ref "RO1A") (pin "2") (pinfunction "2_2") (pintype "passive"))
      (node (ref "RO1B") (pin "1") (pinfunction "1_1") (pintype "passive"))
    )
    (net (code "49") (name "Net-(OI2-A)") (class "Default")
      (node (ref "OI2") (pin "1") (pinfunction "A_1") (pintype "passive"))
      (node (ref "ORIN2") (pin "P$2") (pinfunction "2_P$2") (pintype "passive"))
    )
    (net (code "50") (name "Net-(OI2-COL)") (class "Default")
      (node (ref "OI2") (pin "3") (pinfunction "COL_3") (pintype "passive"))
      (node (ref "RO2A") (pin "2") (pinfunction "2_2") (pintype "passive"))
      (node (ref "RO2B") (pin "1") (pinfunction "1_1") (pintype "passive"))
    )
    (net (code "51") (name "Net-(OI3-A)") (class "Default")
      (node (ref "OI3") (pin "1") (pinfunction "A_1") (pintype "passive"))
      (node (ref "ORIN3") (pin "P$2") (pinfunction "2_P$2") (pintype "passive"))
    )
    (net (code "52") (name "Net-(OI3-COL)") (class "Default")
      (node (ref "OI3") (pin "3") (pinfunction "COL_3") (pintype "passive"))
      (node (ref "RO3A") (pin "2") (pinfunction "2_2") (pintype "passive"))
      (node (ref "RO3B") (pin "1") (pinfunction "1_1") (pintype "passive"))
    )
    (net (code "53") (name "Net-(OI4-A)") (class "Default")
      (node (ref "OI4") (pin "1") (pinfunction "A_1") (pintype "passive"))
      (node (ref "ORIN4") (pin "P$2") (pinfunction "2_P$2") (pintype "passive"))
    )
    (net (code "54") (name "Net-(OI4-COL)") (class "Default")
      (node (ref "OI4") (pin "3") (pinfunction "COL_3") (pintype "passive"))
      (node (ref "RO4A") (pin "2") (pinfunction "2_2") (pintype "passive"))
      (node (ref "RO4B") (pin "1") (pinfunction "1_1") (pintype "passive"))
    )
    (net (code "55") (name "Net-(OI5-A)") (class "Default")
      (node (ref "OI5") (pin "1") (pinfunction "A_1") (pintype "passive"))
      (node (ref "ORIN5") (pin "P$2") (pinfunction "2_P$2") (pintype "passive"))
    )
    (net (code "56") (name "Net-(OI5-COL)") (class "Default")
      (node (ref "OI5") (pin "3") (pinfunction "COL_3") (pintype "passive"))
      (node (ref "RO5A") (pin "2") (pinfunction "2_2") (pintype "passive"))
      (node (ref "RO5B") (pin "1") (pinfunction "1_1") (pintype "passive"))
    )
    (net (code "57") (name "Net-(OI6-A)") (class "Default")
      (node (ref "OI6") (pin "1") (pinfunction "A_1") (pintype "passive"))
      (node (ref "ORIN6") (pin "P$2") (pinfunction "2_P$2") (pintype "passive"))
    )
    (net (code "58") (name "Net-(OI6-COL)") (class "Default")
      (node (ref "OI6") (pin "3") (pinfunction "COL_3") (pintype "passive"))
      (node (ref "RO6A") (pin "2") (pinfunction "2_2") (pintype "passive"))
      (node (ref "RO6B") (pin "1") (pinfunction "1_1") (pintype "passive"))
    )
    (net (code "59") (name "Net-(OI7-A)") (class "Default")
      (node (ref "OI7") (pin "1") (pinfunction "A_1") (pintype "passive"))
      (node (ref "ORIN7") (pin "P$2") (pinfunction "2_P$2") (pintype "passive"))
    )
    (net (code "60") (name "Net-(OI7-COL)") (class "Default")
      (node (ref "OI7") (pin "3") (pinfunction "COL_3") (pintype "passive"))
      (node (ref "RO7A") (pin "2") (pinfunction "2_2") (pintype "passive"))
      (node (ref "RO7B") (pin "1") (pinfunction "1_1") (pintype "passive"))
    )
    (net (code "61") (name "Net-(OI8-A)") (class "Default")
      (node (ref "OI8") (pin "1") (pinfunction "A_1") (pintype "passive"))
      (node (ref "ORIN8") (pin "P$2") (pinfunction "2_P$2") (pintype "passive"))
    )
    (net (code "62") (name "Net-(OI8-COL)") (class "Default")
      (node (ref "OI8") (pin "3") (pinfunction "COL_3") (pintype "passive"))
      (node (ref "RO8A") (pin "2") (pinfunction "2_2") (pintype "passive"))
      (node (ref "RO8B") (pin "1") (pinfunction "1_1") (pintype "passive"))
    )
    (net (code "63") (name "Net-(OI9-A)") (class "Default")
      (node (ref "OI9") (pin "1") (pinfunction "A_1") (pintype "passive"))
      (node (ref "ORIN9") (pin "P$2") (pinfunction "2_P$2") (pintype "passive"))
    )
    (net (code "64") (name "Net-(OI9-COL)") (class "Default")
      (node (ref "OI9") (pin "3") (pinfunction "COL_3") (pintype "passive"))
      (node (ref "RO9A") (pin "2") (pinfunction "2_2") (pintype "passive"))
      (node (ref "RO9B") (pin "1") (pinfunction "1_1") (pintype "passive"))
    )
    (net (code "65") (name "Net-(OI10-A)") (class "Default")
      (node (ref "OI10") (pin "1") (pinfunction "A_1") (pintype "passive"))
      (node (ref "ORIN10") (pin "P$2") (pinfunction "2_P$2") (pintype "passive"))
    )
    (net (code "66") (name "Net-(OI10-COL)") (class "Default")
      (node (ref "OI10") (pin "3") (pinfunction "COL_3") (pintype "passive"))
      (node (ref "RO10A") (pin "2") (pinfunction "2_2") (pintype "passive"))
      (node (ref "RO10B") (pin "1") (pinfunction "1_1") (pintype "passive"))
    )
    (net (code "67") (name "Net-(Q1-IN)") (class "Default")
      (node (ref "Q1") (pin "1") (pinfunction "IN_1") (pintype "input"))
      (node (ref "U$1") (pin "EXTRA23") (pinfunction "EXTRA23_EXTRA23") (pintype "bidirectional"))
    )
    (net (code "68") (name "Net-(Q1-OUT)") (class "Default")
      (node (ref "Q1") (pin "3") (pinfunction "OUT_3") (pintype "output"))
      (node (ref "RO10B") (pin "2") (pinfunction "2_2") (pintype "passive"))
      (node (ref "RO10C") (pin "2") (pinfunction "2_2") (pintype "passive"))
      (node (ref "RO1B") (pin "2") (pinfunction "2_2") (pintype "passive"))
      (node (ref "RO1C") (pin "2") (pinfunction "2_2") (pintype "passive"))
      (node (ref "RO2B") (pin "2") (pinfunction "2_2") (pintype "passive"))
      (node (ref "RO2C") (pin "2") (pinfunction "2_2") (pintype "passive"))
      (node (ref "RO3B") (pin "2") (pinfunction "2_2") (pintype "passive"))
      (node (ref "RO3C") (pin "2") (pinfunction "2_2") (pintype "passive"))
      (node (ref "RO4B") (pin "2") (pinfunction "2_2") (pintype "passive"))
      (node (ref "RO4C") (pin "2") (pinfunction "2_2") (pintype "passive"))
      (node (ref "RO5B") (pin "2") (pinfunction "2_2") (pintype "passive"))
      (node (ref "RO5C") (pin "2") (pinfunction "2_2") (pintype "passive"))
      (node (ref "RO6B") (pin "2") (pinfunction "2_2") (pintype "passive"))
      (node (ref "RO6C") (pin "2") (pinfunction "2_2") (pintype "passive"))
      (node (ref "RO7B") (pin "2") (pinfunction "2_2") (pintype "passive"))
      (node (ref "RO7C") (pin "2") (pinfunction "2_2") (pintype "passive"))
      (node (ref "RO8B") (pin "2") (pinfunction "2_2") (pintype "passive"))
      (node (ref "RO8C") (pin "2") (pinfunction "2_2") (pintype "passive"))
      (node (ref "RO9B") (pin "2") (pinfunction "2_2") (pintype "passive"))
      (node (ref "RO9C") (pin "2") (pinfunction "2_2") (pintype "passive"))
    )
    (net (code "69") (name "Net-(T1-B)") (class "Default")
      (node (ref "RO1A") (pin "1") (pinfunction "1_1") (pintype "passive"))
      (node (ref "T1") (pin "3") (pinfunction "B_3") (pintype "passive"))
    )
    (net (code "70") (name "Net-(T1-C)") (class "Default")
      (node (ref "ESC1") (pin "1") (pinfunction "1_1") (pintype "passive"))
      (node (ref "RO1C") (pin "1") (pinfunction "1_1") (pintype "passive"))
      (node (ref "T1") (pin "2") (pinfunction "C_2") (pintype "passive"))
    )
    (net (code "71") (name "Net-(T2-B)") (class "Default")
      (node (ref "RO2A") (pin "1") (pinfunction "1_1") (pintype "passive"))
      (node (ref "T2") (pin "3") (pinfunction "B_3") (pintype "passive"))
    )
    (net (code "72") (name "Net-(T2-C)") (class "Default")
      (node (ref "ESC2") (pin "1") (pinfunction "1_1") (pintype "passive"))
      (node (ref "RO2C") (pin "1") (pinfunction "1_1") (pintype "passive"))
      (node (ref "T2") (pin "2") (pinfunction "C_2") (pintype "passive"))
    )
    (net (code "73") (name "Net-(T3-B)") (class "Default")
      (node (ref "RO3A") (pin "1") (pinfunction "1_1") (pintype "passive"))
      (node (ref "T3") (pin "3") (pinfunction "B_3") (pintype "passive"))
    )
    (net (code "74") (name "Net-(T3-C)") (class "Default")
      (node (ref "ESC3") (pin "1") (pinfunction "1_1") (pintype "passive"))
      (node (ref "RO3C") (pin "1") (pinfunction "1_1") (pintype "passive"))
      (node (ref "T3") (pin "2") (pinfunction "C_2") (pintype "passive"))
    )
    (net (code "75") (name "Net-(T4-B)") (class "Default")
      (node (ref "RO4A") (pin "1") (pinfunction "1_1") (pintype "passive"))
      (node (ref "T4") (pin "3") (pinfunction "B_3") (pintype "passive"))
    )
    (net (code "76") (name "Net-(T4-C)") (class "Default")
      (node (ref "ESC4") (pin "1") (pinfunction "1_1") (pintype "passive"))
      (node (ref "RO4C") (pin "1") (pinfunction "1_1") (pintype "passive"))
      (node (ref "T4") (pin "2") (pinfunction "C_2") (pintype "passive"))
    )
    (net (code "77") (name "Net-(T5-B)") (class "Default")
      (node (ref "RO5A") (pin "1") (pinfunction "1_1") (pintype "passive"))
      (node (ref "T5") (pin "3") (pinfunction "B_3") (pintype "passive"))
    )
    (net (code "78") (name "Net-(T5-C)") (class "Default")
      (node (ref "ESC5") (pin "1") (pinfunction "1_1") (pintype "passive"))
      (node (ref "RO5C") (pin "1") (pinfunction "1_1") (pintype "passive"))
      (node (ref "T5") (pin "2") (pinfunction "C_2") (pintype "passive"))
    )
    (net (code "79") (name "Net-(T6-B)") (class "Default")
      (node (ref "RO6A") (pin "1") (pinfunction "1_1") (pintype "passive"))
      (node (ref "T6") (pin "3") (pinfunction "B_3") (pintype "passive"))
    )
    (net (code "80") (name "Net-(T6-C)") (class "Default")
      (node (ref "ESC6") (pin "1") (pinfunction "1_1") (pintype "passive"))
      (node (ref "RO6C") (pin "1") (pinfunction "1_1") (pintype "passive"))
      (node (ref "T6") (pin "2") (pinfunction "C_2") (pintype "passive"))
    )
    (net (code "81") (name "Net-(T7-B)") (class "Default")
      (node (ref "RO7A") (pin "1") (pinfunction "1_1") (pintype "passive"))
      (node (ref "T7") (pin "3") (pinfunction "B_3") (pintype "passive"))
    )
    (net (code "82") (name "Net-(T7-C)") (class "Default")
      (node (ref "ESC7") (pin "1") (pinfunction "1_1") (pintype "passive"))
      (node (ref "RO7C") (pin "1") (pinfunction "1_1") (pintype "passive"))
      (node (ref "T7") (pin "2") (pinfunction "C_2") (pintype "passive"))
    )
    (net (code "83") (name "Net-(T8-B)") (class "Default")
      (node (ref "RO8A") (pin "1") (pinfunction "1_1") (pintype "passive"))
      (node (ref "T8") (pin "3") (pinfunction "B_3") (pintype "passive"))
    )
    (net (code "84") (name "Net-(T8-C)") (class "Default")
      (node (ref "ESC8") (pin "1") (pinfunction "1_1") (pintype "passive"))
      (node (ref "RO8C") (pin "1") (pinfunction "1_1") (pintype "passive"))
      (node (ref "T8") (pin "2") (pinfunction "C_2") (pintype "passive"))
    )
    (net (code "85") (name "Net-(T9-B)") (class "Default")
      (node (ref "RO9A") (pin "1") (pinfunction "1_1") (pintype "passive"))
      (node (ref "T9") (pin "3") (pinfunction "B_3") (pintype "passive"))
    )
    (net (code "86") (name "Net-(T9-C)") (class "Default")
      (node (ref "ESC9") (pin "1") (pinfunction "1_1") (pintype "passive"))
      (node (ref "RO9C") (pin "1") (pinfunction "1_1") (pintype "passive"))
      (node (ref "T9") (pin "2") (pinfunction "C_2") (pintype "passive"))
    )
    (net (code "87") (name "Net-(T10-B)") (class "Default")
      (node (ref "RO10A") (pin "1") (pinfunction "1_1") (pintype "passive"))
      (node (ref "T10") (pin "3") (pinfunction "B_3") (pintype "passive"))
    )
    (net (code "88") (name "Net-(T10-C)") (class "Default")
      (node (ref "ESC10") (pin "1") (pinfunction "1_1") (pintype "passive"))
      (node (ref "RO10C") (pin "1") (pinfunction "1_1") (pintype "passive"))
      (node (ref "T10") (pin "2") (pinfunction "C_2") (pintype "passive"))
    )
    (net (code "89") (name "unconnected-(ESC1-Pad2)") (class "Default")
      (node (ref "ESC1") (pin "2") (pinfunction "2_2") (pintype "passive"))
    )
    (net (code "90") (name "unconnected-(ESC2-Pad2)") (class "Default")
      (node (ref "ESC2") (pin "2") (pinfunction "2_2") (pintype "passive"))
    )
    (net (code "91") (name "unconnected-(ESC3-Pad2)") (class "Default")
      (node (ref "ESC3") (pin "2") (pinfunction "2_2") (pintype "passive"))
    )
    (net (code "92") (name "unconnected-(ESC4-Pad2)") (class "Default")
      (node (ref "ESC4") (pin "2") (pinfunction "2_2") (pintype "passive"))
    )
    (net (code "93") (name "unconnected-(ESC5-Pad2)") (class "Default")
      (node (ref "ESC5") (pin "2") (pinfunction "2_2") (pintype "passive"))
    )
    (net (code "94") (name "unconnected-(ESC6-Pad2)") (class "Default")
      (node (ref "ESC6") (pin "2") (pinfunction "2_2") (pintype "passive"))
    )
    (net (code "95") (name "unconnected-(ESC7-Pad2)") (class "Default")
      (node (ref "ESC7") (pin "2") (pinfunction "2_2") (pintype "passive"))
    )
    (net (code "96") (name "unconnected-(ESC8-Pad2)") (class "Default")
      (node (ref "ESC8") (pin "2") (pinfunction "2_2") (pintype "passive"))
    )
    (net (code "97") (name "unconnected-(ESC9-Pad2)") (class "Default")
      (node (ref "ESC9") (pin "2") (pinfunction "2_2") (pintype "passive"))
    )
    (net (code "98") (name "unconnected-(ESC10-Pad2)") (class "Default")
      (node (ref "ESC10") (pin "2") (pinfunction "2_2") (pintype "passive"))
    )
    (net (code "99") (name "unconnected-(IC1-BOOT0-Pad60)") (class "Default")
      (node (ref "IC1") (pin "60") (pinfunction "BOOT0_60") (pintype "passive"))
    )
    (net (code "100") (name "unconnected-(IC1-PA4-Pad20)") (class "Default")
      (node (ref "IC1") (pin "20") (pinfunction "PA4_20") (pintype "passive"))
    )
    (net (code "101") (name "unconnected-(IC1-PA5-Pad21)") (class "Default")
      (node (ref "IC1") (pin "21") (pinfunction "PA5_21") (pintype "passive"))
    )
    (net (code "102") (name "unconnected-(IC1-PA9-Pad42)") (class "Default")
      (node (ref "IC1") (pin "42") (pinfunction "PA9_42") (pintype "passive"))
    )
    (net (code "103") (name "unconnected-(IC1-PA10-Pad43)") (class "Default")
      (node (ref "IC1") (pin "43") (pinfunction "PA10_43") (pintype "passive"))
    )
    (net (code "104") (name "unconnected-(IC1-PA11-Pad44)") (class "Default")
      (node (ref "IC1") (pin "44") (pinfunction "PA11_44") (pintype "passive"))
    )
    (net (code "105") (name "unconnected-(IC1-PA12-Pad45)") (class "Default")
      (node (ref "IC1") (pin "45") (pinfunction "PA12_45") (pintype "passive"))
    )
    (net (code "106") (name "unconnected-(IC1-PB2-Pad28)") (class "Default")
      (node (ref "IC1") (pin "28") (pinfunction "PB2_28") (pintype "passive"))
    )
    (net (code "107") (name "unconnected-(IC1-PB5-Pad57)") (class "Default")
      (node (ref "IC1") (pin "57") (pinfunction "PB5_57") (pintype "passive"))
    )
    (net (code "108") (name "unconnected-(IC1-PB8-Pad61)") (class "Default")
      (node (ref "IC1") (pin "61") (pinfunction "PB8_61") (pintype "passive"))
    )
    (net (code "109") (name "unconnected-(IC1-PB9-Pad62)") (class "Default")
      (node (ref "IC1") (pin "62") (pinfunction "PB9_62") (pintype "passive"))
    )
    (net (code "110") (name "unconnected-(IC1-PB13-Pad34)") (class "Default")
      (node (ref "IC1") (pin "34") (pinfunction "PB13_34") (pintype "passive"))
    )
    (net (code "111") (name "unconnected-(IC1-PC4-Pad24)") (class "Default")
      (node (ref "IC1") (pin "24") (pinfunction "PC4_24") (pintype "passive"))
    )
    (net (code "112") (name "unconnected-(IC1-PC5-Pad25)") (class "Default")
      (node (ref "IC1") (pin "25") (pinfunction "PC5_25") (pintype "passive"))
    )
    (net (code "113") (name "unconnected-(IC1-PC10-Pad51)") (class "Default")
      (node (ref "IC1") (pin "51") (pinfunction "PC10_51") (pintype "passive"))
    )
    (net (code "114") (name "unconnected-(IC1-PC11-Pad52)") (class "Default")
      (node (ref "IC1") (pin "52") (pinfunction "PC11_52") (pintype "passive"))
    )
    (net (code "115") (name "unconnected-(IC1-PC13-Pad2)") (class "Default")
      (node (ref "IC1") (pin "2") (pinfunction "PC13_2") (pintype "passive"))
    )
    (net (code "116") (name "unconnected-(IC1-PC14-Pad3)") (class "Default")
      (node (ref "IC1") (pin "3") (pinfunction "PC14_3") (pintype "passive"))
    )
    (net (code "117") (name "unconnected-(IC1-VBAT-Pad1)") (class "Default")
      (node (ref "IC1") (pin "1") (pinfunction "VBAT_1") (pintype "passive"))
    )
    (net (code "118") (name "unconnected-(J4-Pad11)") (class "Default")
      (node (ref "J4") (pin "11") (pinfunction "11_11") (pintype "passive"))
    )
    (net (code "119") (name "unconnected-(J4-Pad17)") (class "Default")
      (node (ref "J4") (pin "17") (pinfunction "17_17") (pintype "passive"))
    )
    (net (code "120") (name "unconnected-(J4-Pad19)") (class "Default")
      (node (ref "J4") (pin "19") (pinfunction "19_19") (pintype "passive"))
    )
    (net (code "121") (name "unconnected-(J5-CD{slash}DAT3(~{CS})-Pad2)") (class "Default")
      (node (ref "J5") (pin "2") (pinfunction "CD/DAT3(~{CS})_2") (pintype "bidirectional"))
    )
    (net (code "122") (name "unconnected-(J5-DAT1(RSV)-Pad8)") (class "Default")
      (node (ref "J5") (pin "8") (pinfunction "DAT1(RSV)_8") (pintype "bidirectional"))
    )
    (net (code "123") (name "unconnected-(J5-DAT2(NC)-Pad1)") (class "Default")
      (node (ref "J5") (pin "1") (pinfunction "DAT2(NC)_1") (pintype "bidirectional"))
    )
    (net (code "124") (name "unconnected-(J5-PadCD1)") (class "Default")
      (node (ref "J5") (pin "CD1") (pinfunction "CD1_CD1") (pintype "bidirectional"))
    )
    (net (code "125") (name "unconnected-(J5-PadCD2)") (class "Default")
      (node (ref "J5") (pin "CD2") (pinfunction "CD2_CD2") (pintype "bidirectional"))
    )
    (net (code "126") (name "unconnected-(RESET-S-Pad1)") (class "Default")
      (node (ref "RESET") (pin "1") (pinfunction "S_1") (pintype "passive"))
    )
    (net (code "127") (name "unconnected-(U$1-PadCAN_H)") (class "Default")
      (node (ref "U$1") (pin "CAN_H") (pinfunction "CAN_H_CAN_H") (pintype "bidirectional"))
    )
    (net (code "128") (name "unconnected-(U$1-PadCAN_L)") (class "Default")
      (node (ref "U$1") (pin "CAN_L") (pinfunction "CAN_L_CAN_L") (pintype "bidirectional"))
    )
    (net (code "129") (name "unconnected-(U$1-PadEXTRA1)") (class "Default")
      (node (ref "U$1") (pin "EXTRA1") (pinfunction "EXTRA1_EXTRA1") (pintype "bidirectional"))
    )
    (net (code "130") (name "unconnected-(U$1-PadEXTRA2)") (class "Default")
      (node (ref "U$1") (pin "EXTRA2") (pinfunction "EXTRA2_EXTRA2") (pintype "bidirectional"))
    )
    (net (code "131") (name "unconnected-(U$1-PadEXTRA3)") (class "Default")
      (node (ref "U$1") (pin "EXTRA3") (pinfunction "EXTRA3_EXTRA3") (pintype "bidirectional"))
    )
    (net (code "132") (name "unconnected-(U$1-PadEXTRA4)") (class "Default")
      (node (ref "U$1") (pin "EXTRA4") (pinfunction "EXTRA4_EXTRA4") (pintype "bidirectional"))
    )
    (net (code "133") (name "unconnected-(U$1-PadEXTRA5)") (class "Default")
      (node (ref "U$1") (pin "EXTRA5") (pinfunction "EXTRA5_EXTRA5") (pintype "bidirectional"))
    )
    (net (code "134") (name "unconnected-(U$1-PadEXTRA6)") (class "Default")
      (node (ref "U$1") (pin "EXTRA6") (pinfunction "EXTRA6_EXTRA6") (pintype "bidirectional"))
    )
    (net (code "135") (name "unconnected-(U$1-PadEXTRA7)") (class "Default")
      (node (ref "U$1") (pin "EXTRA7") (pinfunction "EXTRA7_EXTRA7") (pintype "bidirectional"))
    )
    (net (code "136") (name "unconnected-(U$1-PadEXTRA8)") (class "Default")
      (node (ref "U$1") (pin "EXTRA8") (pinfunction "EXTRA8_EXTRA8") (pintype "bidirectional"))
    )
    (net (code "137") (name "unconnected-(U$1-PadEXTRA9)") (class "Default")
      (node (ref "U$1") (pin "EXTRA9") (pinfunction "EXTRA9_EXTRA9") (pintype "bidirectional"))
    )
    (net (code "138") (name "unconnected-(U$1-PadEXTRA10)") (class "Default")
      (node (ref "U$1") (pin "EXTRA10") (pinfunction "EXTRA10_EXTRA10") (pintype "bidirectional"))
    )
    (net (code "139") (name "unconnected-(U$1-PadEXTRA11)") (class "Default")
      (node (ref "U$1") (pin "EXTRA11") (pinfunction "EXTRA11_EXTRA11") (pintype "bidirectional"))
    )
    (net (code "140") (name "unconnected-(U$1-PadEXTRA12)") (class "Default")
      (node (ref "U$1") (pin "EXTRA12") (pinfunction "EXTRA12_EXTRA12") (pintype "bidirectional"))
    )
    (net (code "141") (name "unconnected-(U$1-PadEXTRA13)") (class "Default")
      (node (ref "U$1") (pin "EXTRA13") (pinfunction "EXTRA13_EXTRA13") (pintype "bidirectional"))
    )
    (net (code "142") (name "unconnected-(U$1-PadEXTRA14)") (class "Default")
      (node (ref "U$1") (pin "EXTRA14") (pinfunction "EXTRA14_EXTRA14") (pintype "bidirectional"))
    )
    (net (code "143") (name "unconnected-(U$1-PadEXTRA15)") (class "Default")
      (node (ref "U$1") (pin "EXTRA15") (pinfunction "EXTRA15_EXTRA15") (pintype "bidirectional"))
    )
    (net (code "144") (name "unconnected-(U$1-PadEXTRA16)") (class "Default")
      (node (ref "U$1") (pin "EXTRA16") (pinfunction "EXTRA16_EXTRA16") (pintype "bidirectional"))
    )
    (net (code "145") (name "unconnected-(U$1-PadEXTRA17)") (class "Default")
      (node (ref "U$1") (pin "EXTRA17") (pinfunction "EXTRA17_EXTRA17") (pintype "bidirectional"))
    )
    (net (code "146") (name "unconnected-(U$1-PadEXTRA18)") (class "Default")
      (node (ref "U$1") (pin "EXTRA18") (pinfunction "EXTRA18_EXTRA18") (pintype "bidirectional"))
    )
    (net (code "147") (name "unconnected-(U$1-PadEXTRA19)") (class "Default")
      (node (ref "U$1") (pin "EXTRA19") (pinfunction "EXTRA19_EXTRA19") (pintype "bidirectional"))
    )
    (net (code "148") (name "unconnected-(U$1-PadEXTRA20)") (class "Default")
      (node (ref "U$1") (pin "EXTRA20") (pinfunction "EXTRA20_EXTRA20") (pintype "bidirectional"))
    )
    (net (code "149") (name "unconnected-(U$1-PadEXTRA21)") (class "Default")
      (node (ref "U$1") (pin "EXTRA21") (pinfunction "EXTRA21_EXTRA21") (pintype "bidirectional"))
    )
    (net (code "150") (name "unconnected-(U$1-PadEXTRA22)") (class "Default")
      (node (ref "U$1") (pin "EXTRA22") (pinfunction "EXTRA22_EXTRA22") (pintype "bidirectional"))
    )
    (net (code "151") (name "unconnected-(U$1-PadEXTRA25)") (class "Default")
      (node (ref "U$1") (pin "EXTRA25") (pinfunction "EXTRA25_EXTRA25") (pintype "bidirectional"))
    )
    (net (code "152") (name "unconnected-(U$1-PadEXTRA26)") (class "Default")
      (node (ref "U$1") (pin "EXTRA26") (pinfunction "EXTRA26_EXTRA26") (pintype "bidirectional"))
    )
    (net (code "153") (name "unconnected-(U$1-PadEXTRA27)") (class "Default")
      (node (ref "U$1") (pin "EXTRA27") (pinfunction "EXTRA27_EXTRA27") (pintype "bidirectional"))
    )
    (net (code "154") (name "unconnected-(U$1-PadEXTRA28)") (class "Default")
      (node (ref "U$1") (pin "EXTRA28") (pinfunction "EXTRA28_EXTRA28") (pintype "bidirectional"))
    )
    (net (code "155") (name "unconnected-(U$1-PadEXTRA29)") (class "Default")
      (node (ref "U$1") (pin "EXTRA29") (pinfunction "EXTRA29_EXTRA29") (pintype "bidirectional"))
    )
    (net (code "156") (name "unconnected-(U$1-PadEXTRA30)") (class "Default")
      (node (ref "U$1") (pin "EXTRA30") (pinfunction "EXTRA30_EXTRA30") (pintype "bidirectional"))
    )
    (net (code "157") (name "unconnected-(U$1-PadEXTRA31)") (class "Default")
      (node (ref "U$1") (pin "EXTRA31") (pinfunction "EXTRA31_EXTRA31") (pintype "bidirectional"))
    )
    (net (code "158") (name "unconnected-(U$1-PadEXTRA32)") (class "Default")
      (node (ref "U$1") (pin "EXTRA32") (pinfunction "EXTRA32_EXTRA32") (pintype "bidirectional"))
    )
    (net (code "159") (name "unconnected-(U$1-PadEXTRA33)") (class "Default")
      (node (ref "U$1") (pin "EXTRA33") (pinfunction "EXTRA33_EXTRA33") (pintype "bidirectional"))
    )
    (net (code "160") (name "unconnected-(U$1-PadEXTRA34)") (class "Default")
      (node (ref "U$1") (pin "EXTRA34") (pinfunction "EXTRA34_EXTRA34") (pintype "bidirectional"))
    )
    (net (code "161") (name "unconnected-(U$1-PadEXTRA35)") (class "Default")
      (node (ref "U$1") (pin "EXTRA35") (pinfunction "EXTRA35_EXTRA35") (pintype "bidirectional"))
    )
    (net (code "162") (name "unconnected-(U$1-PadSCL_DEPTH)") (class "Default")
      (node (ref "U$1") (pin "SCL_DEPTH") (pinfunction "SCL_DEPTH_SCL_DEPTH") (pintype "bidirectional"))
    )
    (net (code "163") (name "unconnected-(U$1-PadSCL_ESC)") (class "Default")
      (node (ref "U$1") (pin "SCL_ESC") (pinfunction "SCL_ESC_SCL_ESC") (pintype "bidirectional"))
    )
    (net (code "164") (name "unconnected-(U$1-PadSDA_DEPTH)") (class "Default")
      (node (ref "U$1") (pin "SDA_DEPTH") (pinfunction "SDA_DEPTH_SDA_DEPTH") (pintype "bidirectional"))
    )
    (net (code "165") (name "unconnected-(U$1-PadSDA_ESC)") (class "Default")
      (node (ref "U$1") (pin "SDA_ESC") (pinfunction "SDA_ESC_SDA_ESC") (pintype "bidirectional"))
    )
  )
)
